# Power.net
KiCad netlist of a schematic drawn in Altium Designer
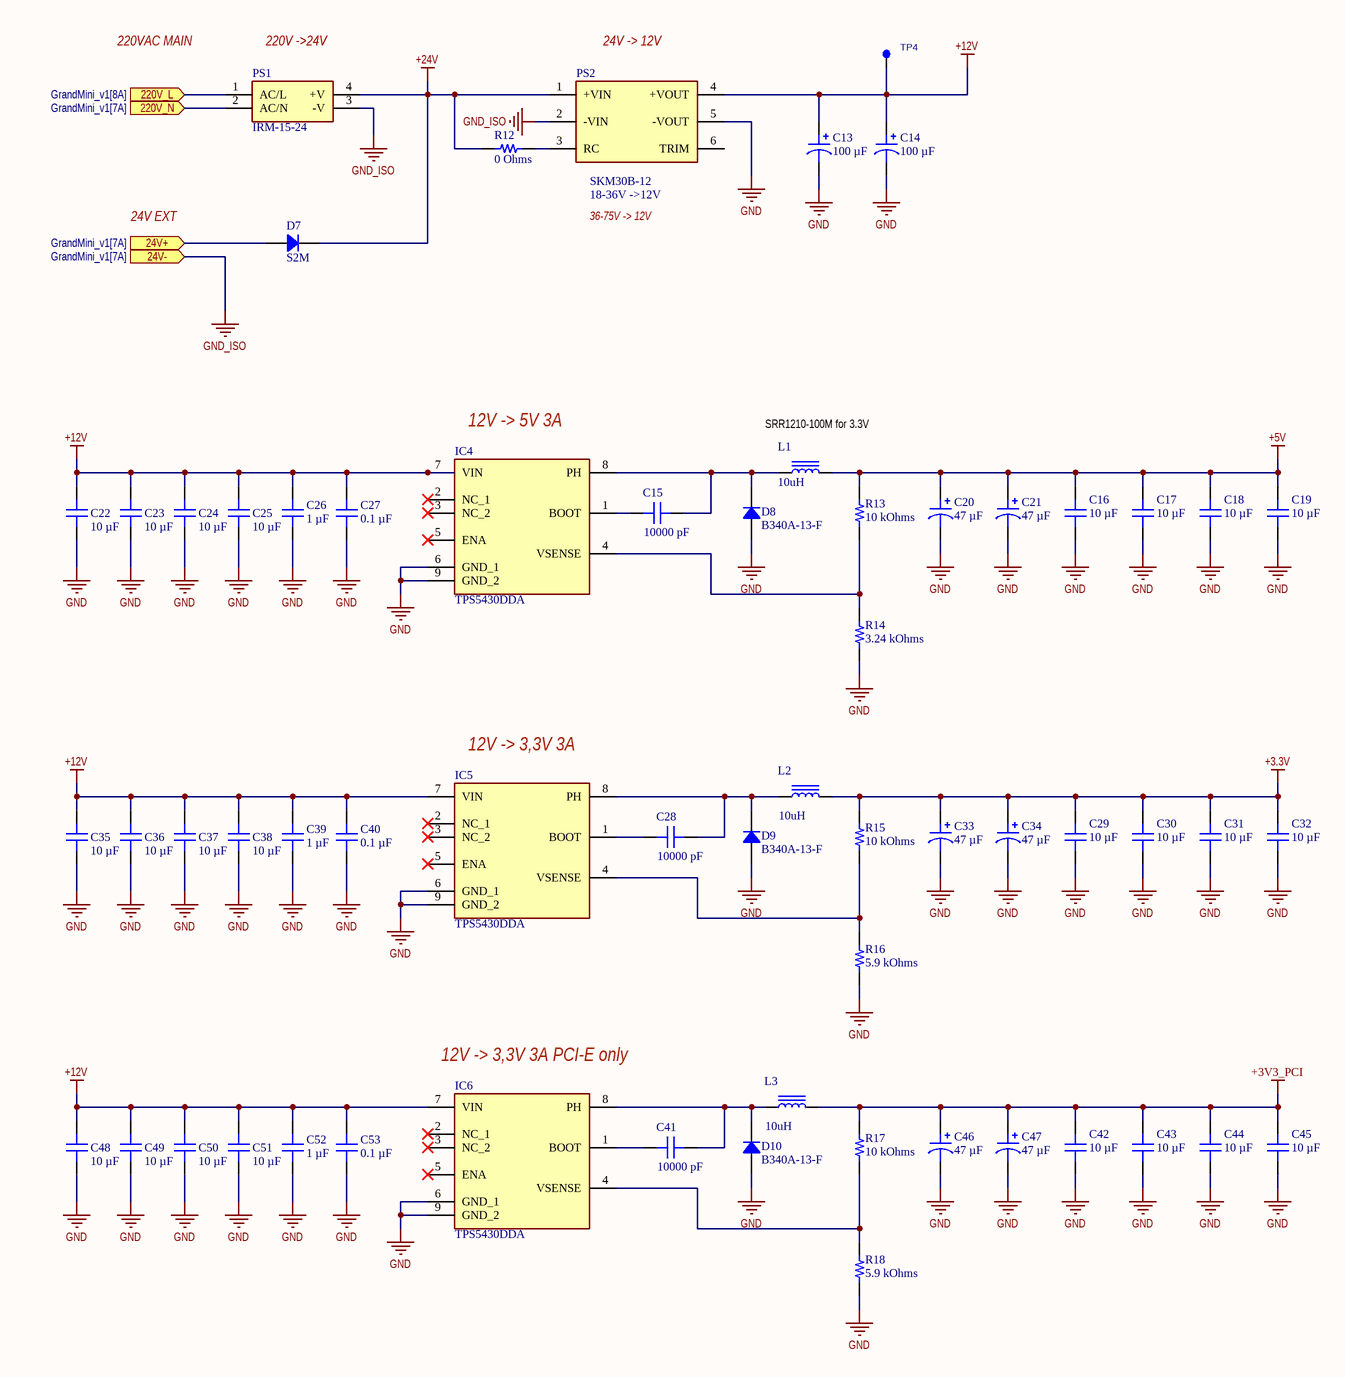
[diagram p0: Power.SchDoc]

(export (version "E")
  (design (tool "Eeschema 10.0.6"))
  (components
    (comp (ref "C13")
      (value "100 µF")
      (footprint "CAP ALSMD 8.3MM H10.5MM")
      (description "CAP ALUM 100UF 20% 35V SMD")
      (fields
        (field (name "PART NUMBER") "EEE-FP1V101AL")
        (field (name "MANUFACTURER") "Panasonic Electronic Components")
      )
      (libsource (lib "Celestial Altium Library - altium_library") (part "Polarised Capacitor"))
    )
    (comp (ref "C14")
      (value "100 µF")
      (footprint "CAP ALSMD 8.3MM H10.5MM")
      (description "CAP ALUM 100UF 20% 35V SMD")
      (fields
        (field (name "PART NUMBER") "EEE-FP1V101AL")
        (field (name "MANUFACTURER") "Panasonic Electronic Components")
      )
      (libsource (lib "Celestial Altium Library - altium_library") (part "Polarised Capacitor"))
    )
    (comp (ref "C15")
      (value "10000 pF")
      (footprint "CAP 0603_1608")
      (description "CAP CER 10000PF 50V X7R 0603")
      (fields (field (name "MANUFACTURER") "Yageo") (field (name "TOLERANCE") "±5%"))
      (libsource (lib "Celestial Altium Library - altium_library") (part "Capacitor"))
    )
    (comp (ref "C16")
      (value "10 µF")
      (footprint "CAP 0805_2012")
      (description "CAP CER 10UF 25V X5R 0805")
      (fields (field (name "PART NUMBER") "CC0805KKX5R8BB106") (field (name "MANUFACTURER") "Yageo"))
      (libsource (lib "Celestial Altium Library - altium_library") (part "Capacitor"))
    )
    (comp (ref "C17")
      (value "10 µF")
      (footprint "CAP 0805_2012")
      (description "CAP CER 10UF 25V X5R 0805")
      (fields (field (name "PART NUMBER") "CC0805KKX5R8BB106") (field (name "MANUFACTURER") "Yageo"))
      (libsource (lib "Celestial Altium Library - altium_library") (part "Capacitor"))
    )
    (comp (ref "C18")
      (value "10 µF")
      (footprint "CAP 0805_2012")
      (description "CAP CER 10UF 25V X5R 0805")
      (fields (field (name "PART NUMBER") "CC0805KKX5R8BB106") (field (name "MANUFACTURER") "Yageo"))
      (libsource (lib "Celestial Altium Library - altium_library") (part "Capacitor"))
    )
    (comp (ref "C19")
      (value "10 µF")
      (footprint "CAP 0805_2012")
      (description "CAP CER 10UF 25V X5R 0805")
      (fields (field (name "PART NUMBER") "CC0805KKX5R8BB106") (field (name "MANUFACTURER") "Yageo"))
      (libsource (lib "Celestial Altium Library - altium_library") (part "Capacitor"))
    )
    (comp (ref "C20")
      (value "47 µF")
      (footprint "CAP POL 2917_7343")
      (description "CAP TANT 47UF 10% 35V 2917")
      (fields (field (name "PART NUMBER") "T491X476K035AT") (field (name "MANUFACTURER") "KEMET"))
      (libsource (lib "Celestial Altium Library - altium_library") (part "Polarised Capacitor"))
    )
    (comp (ref "C21")
      (value "47 µF")
      (footprint "CAP POL 2917_7343")
      (description "CAP TANT 47UF 10% 35V 2917")
      (fields (field (name "PART NUMBER") "T491X476K035AT") (field (name "MANUFACTURER") "KEMET"))
      (libsource (lib "Celestial Altium Library - altium_library") (part "Polarised Capacitor"))
    )
    (comp (ref "C22")
      (value "10 µF")
      (footprint "CAP 0805_2012")
      (description "CAP CER 10UF 25V X5R 0805")
      (fields (field (name "PART NUMBER") "CC0805KKX5R8BB106") (field (name "MANUFACTURER") "Yageo"))
      (libsource (lib "Celestial Altium Library - altium_library") (part "Capacitor"))
    )
    (comp (ref "C23")
      (value "10 µF")
      (footprint "CAP 0805_2012")
      (description "CAP CER 10UF 25V X5R 0805")
      (fields (field (name "PART NUMBER") "CC0805KKX5R8BB106") (field (name "MANUFACTURER") "Yageo"))
      (libsource (lib "Celestial Altium Library - altium_library") (part "Capacitor"))
    )
    (comp (ref "C24")
      (value "10 µF")
      (footprint "CAP 0805_2012")
      (description "CAP CER 10UF 25V X5R 0805")
      (fields (field (name "PART NUMBER") "CC0805KKX5R8BB106") (field (name "MANUFACTURER") "Yageo"))
      (libsource (lib "Celestial Altium Library - altium_library") (part "Capacitor"))
    )
    (comp (ref "C25")
      (value "10 µF")
      (footprint "CAP 0805_2012")
      (description "CAP CER 10UF 25V X5R 0805")
      (fields (field (name "PART NUMBER") "CC0805KKX5R8BB106") (field (name "MANUFACTURER") "Yageo"))
      (libsource (lib "Celestial Altium Library - altium_library") (part "Capacitor"))
    )
    (comp (ref "C26")
      (value "1 µF")
      (footprint "CAP 0603_1608")
      (description "CAP CER 1UF 50V X7R 0603")
      (fields (field (name "PART NUMBER") "CC0603KRX7R9BB105") (field (name "MANUFACTURER") "Yageo"))
      (libsource (lib "Celestial Altium Library - altium_library") (part "Capacitor"))
    )
    (comp (ref "C27")
      (value "0.1 µF")
      (footprint "CAP 0603_1608")
      (description "CAP CER 0.1UF 50V X7R 0603")
      (fields (field (name "PART NUMBER") "CC0603KRX7R9BB104") (field (name "MANUFACTURER") "Yageo"))
      (libsource (lib "Celestial Altium Library - altium_library") (part "Capacitor"))
    )
    (comp (ref "C28")
      (value "10000 pF")
      (footprint "CAP 0603_1608")
      (description "CAP CER 10000PF 50V X7R 0603")
      (fields (field (name "MANUFACTURER") "Yageo") (field (name "TOLERANCE") "±5%"))
      (libsource (lib "Celestial Altium Library - altium_library") (part "Capacitor"))
    )
    (comp (ref "C29")
      (value "10 µF")
      (footprint "CAP 0805_2012")
      (description "CAP CER 10UF 25V X5R 0805")
      (fields (field (name "PART NUMBER") "CC0805KKX5R8BB106") (field (name "MANUFACTURER") "Yageo"))
      (libsource (lib "Celestial Altium Library - altium_library") (part "Capacitor"))
    )
    (comp (ref "C30")
      (value "10 µF")
      (footprint "CAP 0805_2012")
      (description "CAP CER 10UF 25V X5R 0805")
      (fields (field (name "PART NUMBER") "CC0805KKX5R8BB106") (field (name "MANUFACTURER") "Yageo"))
      (libsource (lib "Celestial Altium Library - altium_library") (part "Capacitor"))
    )
    (comp (ref "C31")
      (value "10 µF")
      (footprint "CAP 0805_2012")
      (description "CAP CER 10UF 25V X5R 0805")
      (fields (field (name "PART NUMBER") "CC0805KKX5R8BB106") (field (name "MANUFACTURER") "Yageo"))
      (libsource (lib "Celestial Altium Library - altium_library") (part "Capacitor"))
    )
    (comp (ref "C32")
      (value "10 µF")
      (footprint "CAP 0805_2012")
      (description "CAP CER 10UF 25V X5R 0805")
      (fields (field (name "PART NUMBER") "CC0805KKX5R8BB106") (field (name "MANUFACTURER") "Yageo"))
      (libsource (lib "Celestial Altium Library - altium_library") (part "Capacitor"))
    )
    (comp (ref "C33")
      (value "47 µF")
      (footprint "CAP POL 2917_7343")
      (description "CAP TANT 47UF 10% 35V 2917")
      (fields (field (name "PART NUMBER") "T491X476K035AT") (field (name "MANUFACTURER") "KEMET"))
      (libsource (lib "Celestial Altium Library - altium_library") (part "Polarised Capacitor"))
    )
    (comp (ref "C34")
      (value "47 µF")
      (footprint "CAP POL 2917_7343")
      (description "CAP TANT 47UF 10% 35V 2917")
      (fields (field (name "PART NUMBER") "T491X476K035AT") (field (name "MANUFACTURER") "KEMET"))
      (libsource (lib "Celestial Altium Library - altium_library") (part "Polarised Capacitor"))
    )
    (comp (ref "C35")
      (value "10 µF")
      (footprint "CAP 0805_2012")
      (description "CAP CER 10UF 25V X5R 0805")
      (fields (field (name "PART NUMBER") "CC0805KKX5R8BB106") (field (name "MANUFACTURER") "Yageo"))
      (libsource (lib "Celestial Altium Library - altium_library") (part "Capacitor"))
    )
    (comp (ref "C36")
      (value "10 µF")
      (footprint "CAP 0805_2012")
      (description "CAP CER 10UF 25V X5R 0805")
      (fields (field (name "PART NUMBER") "CC0805KKX5R8BB106") (field (name "MANUFACTURER") "Yageo"))
      (libsource (lib "Celestial Altium Library - altium_library") (part "Capacitor"))
    )
    (comp (ref "C37")
      (value "10 µF")
      (footprint "CAP 0805_2012")
      (description "CAP CER 10UF 25V X5R 0805")
      (fields (field (name "PART NUMBER") "CC0805KKX5R8BB106") (field (name "MANUFACTURER") "Yageo"))
      (libsource (lib "Celestial Altium Library - altium_library") (part "Capacitor"))
    )
    (comp (ref "C38")
      (value "10 µF")
      (footprint "CAP 0805_2012")
      (description "CAP CER 10UF 25V X5R 0805")
      (fields (field (name "PART NUMBER") "CC0805KKX5R8BB106") (field (name "MANUFACTURER") "Yageo"))
      (libsource (lib "Celestial Altium Library - altium_library") (part "Capacitor"))
    )
    (comp (ref "C39")
      (value "1 µF")
      (footprint "CAP 0603_1608")
      (description "CAP CER 1UF 50V X7R 0603")
      (fields (field (name "PART NUMBER") "CC0603KRX7R9BB105") (field (name "MANUFACTURER") "Yageo"))
      (libsource (lib "Celestial Altium Library - altium_library") (part "Capacitor"))
    )
    (comp (ref "C40")
      (value "0.1 µF")
      (footprint "CAP 0603_1608")
      (description "CAP CER 0.1UF 50V X7R 0603")
      (fields (field (name "PART NUMBER") "CC0603KRX7R9BB104") (field (name "MANUFACTURER") "Yageo"))
      (libsource (lib "Celestial Altium Library - altium_library") (part "Capacitor"))
    )
    (comp (ref "C41")
      (value "10000 pF")
      (footprint "CAP 0603_1608")
      (description "CAP CER 10000PF 50V X7R 0603")
      (fields (field (name "MANUFACTURER") "Yageo") (field (name "TOLERANCE") "±5%"))
      (libsource (lib "Celestial Altium Library - altium_library") (part "Capacitor"))
    )
    (comp (ref "C42")
      (value "10 µF")
      (footprint "CAP 0805_2012")
      (description "CAP CER 10UF 25V X5R 0805")
      (fields (field (name "PART NUMBER") "CC0805KKX5R8BB106") (field (name "MANUFACTURER") "Yageo"))
      (libsource (lib "Celestial Altium Library - altium_library") (part "Capacitor"))
    )
    (comp (ref "C43")
      (value "10 µF")
      (footprint "CAP 0805_2012")
      (description "CAP CER 10UF 25V X5R 0805")
      (fields (field (name "PART NUMBER") "CC0805KKX5R8BB106") (field (name "MANUFACTURER") "Yageo"))
      (libsource (lib "Celestial Altium Library - altium_library") (part "Capacitor"))
    )
    (comp (ref "C44")
      (value "10 µF")
      (footprint "CAP 0805_2012")
      (description "CAP CER 10UF 25V X5R 0805")
      (fields (field (name "PART NUMBER") "CC0805KKX5R8BB106") (field (name "MANUFACTURER") "Yageo"))
      (libsource (lib "Celestial Altium Library - altium_library") (part "Capacitor"))
    )
    (comp (ref "C45")
      (value "10 µF")
      (footprint "CAP 0805_2012")
      (description "CAP CER 10UF 25V X5R 0805")
      (fields (field (name "PART NUMBER") "CC0805KKX5R8BB106") (field (name "MANUFACTURER") "Yageo"))
      (libsource (lib "Celestial Altium Library - altium_library") (part "Capacitor"))
    )
    (comp (ref "C46")
      (value "47 µF")
      (footprint "CAP POL 2917_7343")
      (description "CAP TANT 47UF 10% 35V 2917")
      (fields (field (name "PART NUMBER") "T491X476K035AT") (field (name "MANUFACTURER") "KEMET"))
      (libsource (lib "Celestial Altium Library - altium_library") (part "Polarised Capacitor"))
    )
    (comp (ref "C47")
      (value "47 µF")
      (footprint "CAP POL 2917_7343")
      (description "CAP TANT 47UF 10% 35V 2917")
      (fields (field (name "PART NUMBER") "T491X476K035AT") (field (name "MANUFACTURER") "KEMET"))
      (libsource (lib "Celestial Altium Library - altium_library") (part "Polarised Capacitor"))
    )
    (comp (ref "C48")
      (value "10 µF")
      (footprint "CAP 0805_2012")
      (description "CAP CER 10UF 25V X5R 0805")
      (fields (field (name "PART NUMBER") "CC0805KKX5R8BB106") (field (name "MANUFACTURER") "Yageo"))
      (libsource (lib "Celestial Altium Library - altium_library") (part "Capacitor"))
    )
    (comp (ref "C49")
      (value "10 µF")
      (footprint "CAP 0805_2012")
      (description "CAP CER 10UF 25V X5R 0805")
      (fields (field (name "PART NUMBER") "CC0805KKX5R8BB106") (field (name "MANUFACTURER") "Yageo"))
      (libsource (lib "Celestial Altium Library - altium_library") (part "Capacitor"))
    )
    (comp (ref "C50")
      (value "10 µF")
      (footprint "CAP 0805_2012")
      (description "CAP CER 10UF 25V X5R 0805")
      (fields (field (name "PART NUMBER") "CC0805KKX5R8BB106") (field (name "MANUFACTURER") "Yageo"))
      (libsource (lib "Celestial Altium Library - altium_library") (part "Capacitor"))
    )
    (comp (ref "C51")
      (value "10 µF")
      (footprint "CAP 0805_2012")
      (description "CAP CER 10UF 25V X5R 0805")
      (fields (field (name "PART NUMBER") "CC0805KKX5R8BB106") (field (name "MANUFACTURER") "Yageo"))
      (libsource (lib "Celestial Altium Library - altium_library") (part "Capacitor"))
    )
    (comp (ref "C52")
      (value "1 µF")
      (footprint "CAP 0603_1608")
      (description "CAP CER 1UF 50V X7R 0603")
      (fields (field (name "PART NUMBER") "CC0603KRX7R9BB105") (field (name "MANUFACTURER") "Yageo"))
      (libsource (lib "Celestial Altium Library - altium_library") (part "Capacitor"))
    )
    (comp (ref "C53")
      (value "0.1 µF")
      (footprint "CAP 0603_1608")
      (description "CAP CER 0.1UF 50V X7R 0603")
      (fields (field (name "PART NUMBER") "CC0603KRX7R9BB104") (field (name "MANUFACTURER") "Yageo"))
      (libsource (lib "Celestial Altium Library - altium_library") (part "Capacitor"))
    )
    (comp (ref "D7")
      (value "S2M")
      (footprint "DO214AA SMB")
      (description "DIODE GEN PURP 1KV 2A DO214AA")
      (fields (field (name "MANUFACTURER") "ON Semiconductor"))
      (libsource (lib "Celestial Altium Library - altium_library") (part "Diode"))
    )
    (comp (ref "D8")
      (value "B340A-13-F")
      (footprint "DO214AC SMA")
      (description "DIODE SCHOTTKY 40V 3A SMA")
      (fields (field (name "MANUFACTURER") "Diodes Incorporated"))
      (libsource (lib "Celestial Altium Library - altium_library") (part "Diode"))
    )
    (comp (ref "D9")
      (value "B340A-13-F")
      (footprint "DO214AC SMA")
      (description "DIODE SCHOTTKY 40V 3A SMA")
      (fields (field (name "MANUFACTURER") "Diodes Incorporated"))
      (libsource (lib "Celestial Altium Library - altium_library") (part "Diode"))
    )
    (comp (ref "D10")
      (value "B340A-13-F")
      (footprint "DO214AC SMA")
      (description "DIODE SCHOTTKY 40V 3A SMA")
      (fields (field (name "MANUFACTURER") "Diodes Incorporated"))
      (libsource (lib "Celestial Altium Library - altium_library") (part "Diode"))
    )
    (comp (ref "IC4")
      (value "TPS5430DDA")
      (footprint "SamacSys:SOIC127P600X170-9N")
      (description "Integrated Circuit")
      (fields (field (name "MOUSER PART NUMBER") "595-TPS5430DDA"))
      (libsource (lib "SamacSys") (part "TPS5430DDA"))
    )
    (comp (ref "IC5")
      (value "TPS5430DDA")
      (footprint "SamacSys:SOIC127P600X170-9N")
      (description "Integrated Circuit")
      (fields (field (name "MOUSER PART NUMBER") "595-TPS5430DDA"))
      (libsource (lib "SamacSys") (part "TPS5430DDA"))
    )
    (comp (ref "IC6")
      (value "TPS5430DDA")
      (footprint "SamacSys:SOIC127P600X170-9N")
      (description "Integrated Circuit")
      (fields (field (name "MOUSER PART NUMBER") "595-TPS5430DDA"))
      (libsource (lib "SamacSys") (part "TPS5430DDA"))
    )
    (comp (ref "L1")
      (value "10uH")
      (footprint "XAL6060-103MEB")
      (description "SMT Inductor")
      (libsource (lib "SamacSys") (part "XAL6060-103MEB"))
    )
    (comp (ref "L2")
      (value "10uH")
      (footprint "XAL6060-103MEB")
      (description "SMT Inductor")
      (libsource (lib "SamacSys") (part "XAL6060-103MEB"))
    )
    (comp (ref "L3")
      (value "10uH")
      (footprint "XAL6060-103MEB")
      (description "SMT Inductor")
      (libsource (lib "SamacSys") (part "XAL6060-103MEB"))
    )
    (comp (ref "PS1")
      (value "IRM-15-24")
      (footprint "SamacSys:IRM-15")
      (description "Power Supply")
      (fields (field (name "MOUSER PART NUMBER") "709-IRM15-24"))
      (libsource (lib "SamacSys") (part "IRM-15-24"))
    )
    (comp (ref "PS2")
      (value "18-36V ->12V")
      (footprint "SamacSys:SKM30")
      (description "DC/DC, 30Вт, Uвх: 18-36В, Uвых: 12ВDC, Iвых: 2,5А\r\nA: 9 ~ 18VDC B: 18 ~ 36VDC C: 36 ~ 75VDC")
      (fields
        (field (name "MANUFACTURER_PART_NUMBER") "SKM30B-12")
        (field (name "MOUSER PART NUMBER") "709-DPU01N-12")
        (field (name "ARROW PART NUMBER") "DPU01N-12")
      )
      (libsource (lib "SamacSys") (part "SKM30B-12"))
    )
    (comp (ref "R12")
      (value "0 Ohms")
      (footprint "YAGEO RES 0603_1608")
      (description "RES 0 OHM JUMPER 1/10W 0603")
      (fields (field (name "PART NUMBER") "RC0603FR-070RL") (field (name "MANUFACTURER") "Yageo"))
      (libsource (lib "Celestial Altium Library - altium_library") (part "Resistor"))
    )
    (comp (ref "R13")
      (value "10 kOhms")
      (footprint "YAGEO RES 0603_1608")
      (description "RES 10K OHM 1% 1/10W 0603")
      (fields (field (name "PART NUMBER") "RC0603FR-0710KL") (field (name "MANUFACTURER") "Yageo"))
      (libsource (lib "Celestial Altium Library - altium_library") (part "Resistor"))
    )
    (comp (ref "R14")
      (value "3.24 kOhms")
      (footprint "YAGEO RES 0603_1608")
      (description "RES 3.24K OHM 1% 1/10W 0603")
      (fields (field (name "PART NUMBER") "RC0603FR-073K24L") (field (name "MANUFACTURER") "Yageo"))
      (libsource (lib "Celestial Altium Library - altium_library") (part "Resistor"))
    )
    (comp (ref "R15")
      (value "10 kOhms")
      (footprint "YAGEO RES 0603_1608")
      (description "RES 10K OHM 1% 1/10W 0603")
      (fields (field (name "PART NUMBER") "RC0603FR-0710KL") (field (name "MANUFACTURER") "Yageo"))
      (libsource (lib "Celestial Altium Library - altium_library") (part "Resistor"))
    )
    (comp (ref "R16")
      (value "5.9 kOhms")
      (footprint "YAGEO RES 0603_1608")
      (description "RES 5.9K OHM 1% 1/10W 0603")
      (fields (field (name "PART NUMBER") "RC0603FR-075K9L") (field (name "MANUFACTURER") "Yageo"))
      (libsource (lib "Celestial Altium Library - altium_library") (part "Resistor"))
    )
    (comp (ref "R17")
      (value "10 kOhms")
      (footprint "YAGEO RES 0603_1608")
      (description "RES 10K OHM 1% 1/10W 0603")
      (fields (field (name "PART NUMBER") "RC0603FR-0710KL") (field (name "MANUFACTURER") "Yageo"))
      (libsource (lib "Celestial Altium Library - altium_library") (part "Resistor"))
    )
    (comp (ref "R18")
      (value "5.9 kOhms")
      (footprint "YAGEO RES 0603_1608")
      (description "RES 5.9K OHM 1% 1/10W 0603")
      (fields (field (name "PART NUMBER") "RC0603FR-075K9L") (field (name "MANUFACTURER") "Yageo"))
      (libsource (lib "Celestial Altium Library - altium_library") (part "Resistor"))
    )
    (comp (ref "TP4")
      (value "PAD_TEST")
      (footprint "Samacsys:PAD_TEST")
      (description "Test Point")
      (fields (field (name "TOLERANCE") "{Tolerance}") (field (name "MANUFACTURER") "{Manufacturer}"))
      (libsource (lib "SamacSys") (part "PAD_TEST"))
    )
  )
  (nets
    (net (code "1") (name "+3.3V") (class "Default")
      (node (ref "C29") (pin "2") (pinfunction "2_2") (pintype "passive"))
      (node (ref "C30") (pin "2") (pinfunction "2_2") (pintype "passive"))
      (node (ref "C31") (pin "2") (pinfunction "2_2") (pintype "passive"))
      (node (ref "C32") (pin "2") (pinfunction "2_2") (pintype "passive"))
      (node (ref "C33") (pin "1") (pinfunction "1_1") (pintype "passive"))
      (node (ref "C34") (pin "1") (pinfunction "1_1") (pintype "passive"))
      (node (ref "L2") (pin "2") (pinfunction "2_2") (pintype "passive"))
      (node (ref "R15") (pin "2") (pinfunction "2_2") (pintype "passive"))
    )
    (net (code "2") (name "+3V3_PCI") (class "Default")
      (node (ref "C42") (pin "2") (pinfunction "2_2") (pintype "passive"))
      (node (ref "C43") (pin "2") (pinfunction "2_2") (pintype "passive"))
      (node (ref "C44") (pin "2") (pinfunction "2_2") (pintype "passive"))
      (node (ref "C45") (pin "2") (pinfunction "2_2") (pintype "passive"))
      (node (ref "C46") (pin "1") (pinfunction "1_1") (pintype "passive"))
      (node (ref "C47") (pin "1") (pinfunction "1_1") (pintype "passive"))
      (node (ref "L3") (pin "2") (pinfunction "2_2") (pintype "passive"))
      (node (ref "R17") (pin "2") (pinfunction "2_2") (pintype "passive"))
    )
    (net (code "3") (name "+5V") (class "Default")
      (node (ref "C16") (pin "2") (pinfunction "2_2") (pintype "passive"))
      (node (ref "C17") (pin "2") (pinfunction "2_2") (pintype "passive"))
      (node (ref "C18") (pin "2") (pinfunction "2_2") (pintype "passive"))
      (node (ref "C19") (pin "2") (pinfunction "2_2") (pintype "passive"))
      (node (ref "C20") (pin "1") (pinfunction "1_1") (pintype "passive"))
      (node (ref "C21") (pin "1") (pinfunction "1_1") (pintype "passive"))
      (node (ref "L1") (pin "2") (pinfunction "2_2") (pintype "passive"))
      (node (ref "R13") (pin "2") (pinfunction "2_2") (pintype "passive"))
    )
    (net (code "4") (name "+12V") (class "Default")
      (node (ref "C13") (pin "1") (pinfunction "1_1") (pintype "passive"))
      (node (ref "C14") (pin "1") (pinfunction "1_1") (pintype "passive"))
      (node (ref "C22") (pin "2") (pinfunction "2_2") (pintype "passive"))
      (node (ref "C23") (pin "2") (pinfunction "2_2") (pintype "passive"))
      (node (ref "C24") (pin "2") (pinfunction "2_2") (pintype "passive"))
      (node (ref "C25") (pin "2") (pinfunction "2_2") (pintype "passive"))
      (node (ref "C26") (pin "2") (pinfunction "2_2") (pintype "passive"))
      (node (ref "C27") (pin "2") (pinfunction "2_2") (pintype "passive"))
      (node (ref "C35") (pin "2") (pinfunction "2_2") (pintype "passive"))
      (node (ref "C36") (pin "2") (pinfunction "2_2") (pintype "passive"))
      (node (ref "C37") (pin "2") (pinfunction "2_2") (pintype "passive"))
      (node (ref "C38") (pin "2") (pinfunction "2_2") (pintype "passive"))
      (node (ref "C39") (pin "2") (pinfunction "2_2") (pintype "passive"))
      (node (ref "C40") (pin "2") (pinfunction "2_2") (pintype "passive"))
      (node (ref "C48") (pin "2") (pinfunction "2_2") (pintype "passive"))
      (node (ref "C49") (pin "2") (pinfunction "2_2") (pintype "passive"))
      (node (ref "C50") (pin "2") (pinfunction "2_2") (pintype "passive"))
      (node (ref "C51") (pin "2") (pinfunction "2_2") (pintype "passive"))
      (node (ref "C52") (pin "2") (pinfunction "2_2") (pintype "passive"))
      (node (ref "C53") (pin "2") (pinfunction "2_2") (pintype "passive"))
      (node (ref "IC4") (pin "7") (pinfunction "VIN_7") (pintype "passive"))
      (node (ref "IC5") (pin "7") (pinfunction "VIN_7") (pintype "passive"))
      (node (ref "IC6") (pin "7") (pinfunction "VIN_7") (pintype "passive"))
      (node (ref "PS2") (pin "4") (pinfunction "+VOUT_4") (pintype "passive"))
      (node (ref "TP4") (pin "1") (pinfunction "1_1") (pintype "passive"))
    )
    (net (code "5") (name "+24V") (class "Default")
      (node (ref "D7") (pin "2") (pinfunction "2_2") (pintype "passive"))
      (node (ref "PS1") (pin "4") (pinfunction "+V_4") (pintype "passive"))
      (node (ref "PS2") (pin "1") (pinfunction "+VIN_1") (pintype "passive"))
      (node (ref "R12") (pin "1") (pinfunction "1_1") (pintype "passive"))
    )
    (net (code "6") (name "/24V+") (class "Default")
      (node (ref "D7") (pin "1") (pinfunction "1_1") (pintype "passive"))
    )
    (net (code "7") (name "/220V_L") (class "Default")
      (node (ref "PS1") (pin "1") (pinfunction "AC/L_1") (pintype "passive"))
    )
    (net (code "8") (name "/220V_N") (class "Default")
      (node (ref "PS1") (pin "2") (pinfunction "AC/N_2") (pintype "passive"))
    )
    (net (code "9") (name "GND") (class "Default")
      (node (ref "C13") (pin "2") (pinfunction "2_2") (pintype "passive"))
      (node (ref "C14") (pin "2") (pinfunction "2_2") (pintype "passive"))
      (node (ref "C16") (pin "1") (pinfunction "1_1") (pintype "passive"))
      (node (ref "C17") (pin "1") (pinfunction "1_1") (pintype "passive"))
      (node (ref "C18") (pin "1") (pinfunction "1_1") (pintype "passive"))
      (node (ref "C19") (pin "1") (pinfunction "1_1") (pintype "passive"))
      (node (ref "C20") (pin "2") (pinfunction "2_2") (pintype "passive"))
      (node (ref "C21") (pin "2") (pinfunction "2_2") (pintype "passive"))
      (node (ref "C22") (pin "1") (pinfunction "1_1") (pintype "passive"))
      (node (ref "C23") (pin "1") (pinfunction "1_1") (pintype "passive"))
      (node (ref "C24") (pin "1") (pinfunction "1_1") (pintype "passive"))
      (node (ref "C25") (pin "1") (pinfunction "1_1") (pintype "passive"))
      (node (ref "C26") (pin "1") (pinfunction "1_1") (pintype "passive"))
      (node (ref "C27") (pin "1") (pinfunction "1_1") (pintype "passive"))
      (node (ref "C29") (pin "1") (pinfunction "1_1") (pintype "passive"))
      (node (ref "C30") (pin "1") (pinfunction "1_1") (pintype "passive"))
      (node (ref "C31") (pin "1") (pinfunction "1_1") (pintype "passive"))
      (node (ref "C32") (pin "1") (pinfunction "1_1") (pintype "passive"))
      (node (ref "C33") (pin "2") (pinfunction "2_2") (pintype "passive"))
      (node (ref "C34") (pin "2") (pinfunction "2_2") (pintype "passive"))
      (node (ref "C35") (pin "1") (pinfunction "1_1") (pintype "passive"))
      (node (ref "C36") (pin "1") (pinfunction "1_1") (pintype "passive"))
      (node (ref "C37") (pin "1") (pinfunction "1_1") (pintype "passive"))
      (node (ref "C38") (pin "1") (pinfunction "1_1") (pintype "passive"))
      (node (ref "C39") (pin "1") (pinfunction "1_1") (pintype "passive"))
      (node (ref "C40") (pin "1") (pinfunction "1_1") (pintype "passive"))
      (node (ref "C42") (pin "1") (pinfunction "1_1") (pintype "passive"))
      (node (ref "C43") (pin "1") (pinfunction "1_1") (pintype "passive"))
      (node (ref "C44") (pin "1") (pinfunction "1_1") (pintype "passive"))
      (node (ref "C45") (pin "1") (pinfunction "1_1") (pintype "passive"))
      (node (ref "C46") (pin "2") (pinfunction "2_2") (pintype "passive"))
      (node (ref "C47") (pin "2") (pinfunction "2_2") (pintype "passive"))
      (node (ref "C48") (pin "1") (pinfunction "1_1") (pintype "passive"))
      (node (ref "C49") (pin "1") (pinfunction "1_1") (pintype "passive"))
      (node (ref "C50") (pin "1") (pinfunction "1_1") (pintype "passive"))
      (node (ref "C51") (pin "1") (pinfunction "1_1") (pintype "passive"))
      (node (ref "C52") (pin "1") (pinfunction "1_1") (pintype "passive"))
      (node (ref "C53") (pin "1") (pinfunction "1_1") (pintype "passive"))
      (node (ref "D10") (pin "1") (pinfunction "1_1") (pintype "passive"))
      (node (ref "D8") (pin "1") (pinfunction "1_1") (pintype "passive"))
      (node (ref "D9") (pin "1") (pinfunction "1_1") (pintype "passive"))
      (node (ref "IC4") (pin "6") (pinfunction "GND_1_6") (pintype "passive"))
      (node (ref "IC4") (pin "9") (pinfunction "GND_2_9") (pintype "passive"))
      (node (ref "IC5") (pin "6") (pinfunction "GND_1_6") (pintype "passive"))
      (node (ref "IC5") (pin "9") (pinfunction "GND_2_9") (pintype "passive"))
      (node (ref "IC6") (pin "6") (pinfunction "GND_1_6") (pintype "passive"))
      (node (ref "IC6") (pin "9") (pinfunction "GND_2_9") (pintype "passive"))
      (node (ref "PS2") (pin "5") (pinfunction "-VOUT_5") (pintype "passive"))
      (node (ref "R14") (pin "1") (pinfunction "1_1") (pintype "passive"))
      (node (ref "R16") (pin "1") (pinfunction "1_1") (pintype "passive"))
      (node (ref "R18") (pin "1") (pinfunction "1_1") (pintype "passive"))
    )
    (net (code "10") (name "GND_ISO") (class "Default")
      (node (ref "PS1") (pin "3") (pinfunction "-V_3") (pintype "passive"))
      (node (ref "PS2") (pin "2") (pinfunction "-VIN_2") (pintype "passive"))
    )
    (net (code "11") (name "Net-(IC4-BOOT)") (class "Default")
      (node (ref "C15") (pin "2") (pinfunction "2_2") (pintype "passive"))
      (node (ref "IC4") (pin "1") (pinfunction "BOOT_1") (pintype "passive"))
    )
    (net (code "12") (name "Net-(IC4-PH)") (class "Default")
      (node (ref "C15") (pin "1") (pinfunction "1_1") (pintype "passive"))
      (node (ref "D8") (pin "2") (pinfunction "2_2") (pintype "passive"))
      (node (ref "IC4") (pin "8") (pinfunction "PH_8") (pintype "passive"))
      (node (ref "L1") (pin "1") (pinfunction "1_1") (pintype "passive"))
    )
    (net (code "13") (name "Net-(IC4-VSENSE)") (class "Default")
      (node (ref "IC4") (pin "4") (pinfunction "VSENSE_4") (pintype "passive"))
      (node (ref "R13") (pin "1") (pinfunction "1_1") (pintype "passive"))
      (node (ref "R14") (pin "2") (pinfunction "2_2") (pintype "passive"))
    )
    (net (code "14") (name "Net-(IC5-BOOT)") (class "Default")
      (node (ref "C28") (pin "2") (pinfunction "2_2") (pintype "passive"))
      (node (ref "IC5") (pin "1") (pinfunction "BOOT_1") (pintype "passive"))
    )
    (net (code "15") (name "Net-(IC5-PH)") (class "Default")
      (node (ref "C28") (pin "1") (pinfunction "1_1") (pintype "passive"))
      (node (ref "D9") (pin "2") (pinfunction "2_2") (pintype "passive"))
      (node (ref "IC5") (pin "8") (pinfunction "PH_8") (pintype "passive"))
      (node (ref "L2") (pin "1") (pinfunction "1_1") (pintype "passive"))
    )
    (net (code "16") (name "Net-(IC5-VSENSE)") (class "Default")
      (node (ref "IC5") (pin "4") (pinfunction "VSENSE_4") (pintype "passive"))
      (node (ref "R15") (pin "1") (pinfunction "1_1") (pintype "passive"))
      (node (ref "R16") (pin "2") (pinfunction "2_2") (pintype "passive"))
    )
    (net (code "17") (name "Net-(IC6-BOOT)") (class "Default")
      (node (ref "C41") (pin "2") (pinfunction "2_2") (pintype "passive"))
      (node (ref "IC6") (pin "1") (pinfunction "BOOT_1") (pintype "passive"))
    )
    (net (code "18") (name "Net-(IC6-PH)") (class "Default")
      (node (ref "C41") (pin "1") (pinfunction "1_1") (pintype "passive"))
      (node (ref "D10") (pin "2") (pinfunction "2_2") (pintype "passive"))
      (node (ref "IC6") (pin "8") (pinfunction "PH_8") (pintype "passive"))
      (node (ref "L3") (pin "1") (pinfunction "1_1") (pintype "passive"))
    )
    (net (code "19") (name "Net-(IC6-VSENSE)") (class "Default")
      (node (ref "IC6") (pin "4") (pinfunction "VSENSE_4") (pintype "passive"))
      (node (ref "R17") (pin "1") (pinfunction "1_1") (pintype "passive"))
      (node (ref "R18") (pin "2") (pinfunction "2_2") (pintype "passive"))
    )
    (net (code "20") (name "Net-(PS2-RC)") (class "Default")
      (node (ref "PS2") (pin "3") (pinfunction "RC_3") (pintype "passive"))
      (node (ref "R12") (pin "2") (pinfunction "2_2") (pintype "passive"))
    )
    (net (code "21") (name "unconnected-(IC4-ENA-Pad5)") (class "Default")
      (node (ref "IC4") (pin "5") (pinfunction "ENA_5") (pintype "passive+no_connect"))
    )
    (net (code "22") (name "unconnected-(IC4-NC_1-Pad2)") (class "Default")
      (node (ref "IC4") (pin "2") (pinfunction "NC_1_2") (pintype "passive+no_connect"))
    )
    (net (code "23") (name "unconnected-(IC4-NC_2-Pad3)") (class "Default")
      (node (ref "IC4") (pin "3") (pinfunction "NC_2_3") (pintype "passive+no_connect"))
    )
    (net (code "24") (name "unconnected-(IC5-ENA-Pad5)") (class "Default")
      (node (ref "IC5") (pin "5") (pinfunction "ENA_5") (pintype "passive+no_connect"))
    )
    (net (code "25") (name "unconnected-(IC5-NC_1-Pad2)") (class "Default")
      (node (ref "IC5") (pin "2") (pinfunction "NC_1_2") (pintype "passive+no_connect"))
    )
    (net (code "26") (name "unconnected-(IC5-NC_2-Pad3)") (class "Default")
      (node (ref "IC5") (pin "3") (pinfunction "NC_2_3") (pintype "passive+no_connect"))
    )
    (net (code "27") (name "unconnected-(IC6-ENA-Pad5)") (class "Default")
      (node (ref "IC6") (pin "5") (pinfunction "ENA_5") (pintype "passive+no_connect"))
    )
    (net (code "28") (name "unconnected-(IC6-NC_1-Pad2)") (class "Default")
      (node (ref "IC6") (pin "2") (pinfunction "NC_1_2") (pintype "passive+no_connect"))
    )
    (net (code "29") (name "unconnected-(IC6-NC_2-Pad3)") (class "Default")
      (node (ref "IC6") (pin "3") (pinfunction "NC_2_3") (pintype "passive+no_connect"))
    )
    (net (code "30") (name "unconnected-(PS2-TRIM-Pad6)") (class "Default")
      (node (ref "PS2") (pin "6") (pinfunction "TRIM_6") (pintype "passive"))
    )
  )
)
